# SCH_TRAILDEV.net
KiCad netlist of a schematic drawn in EasyEDA
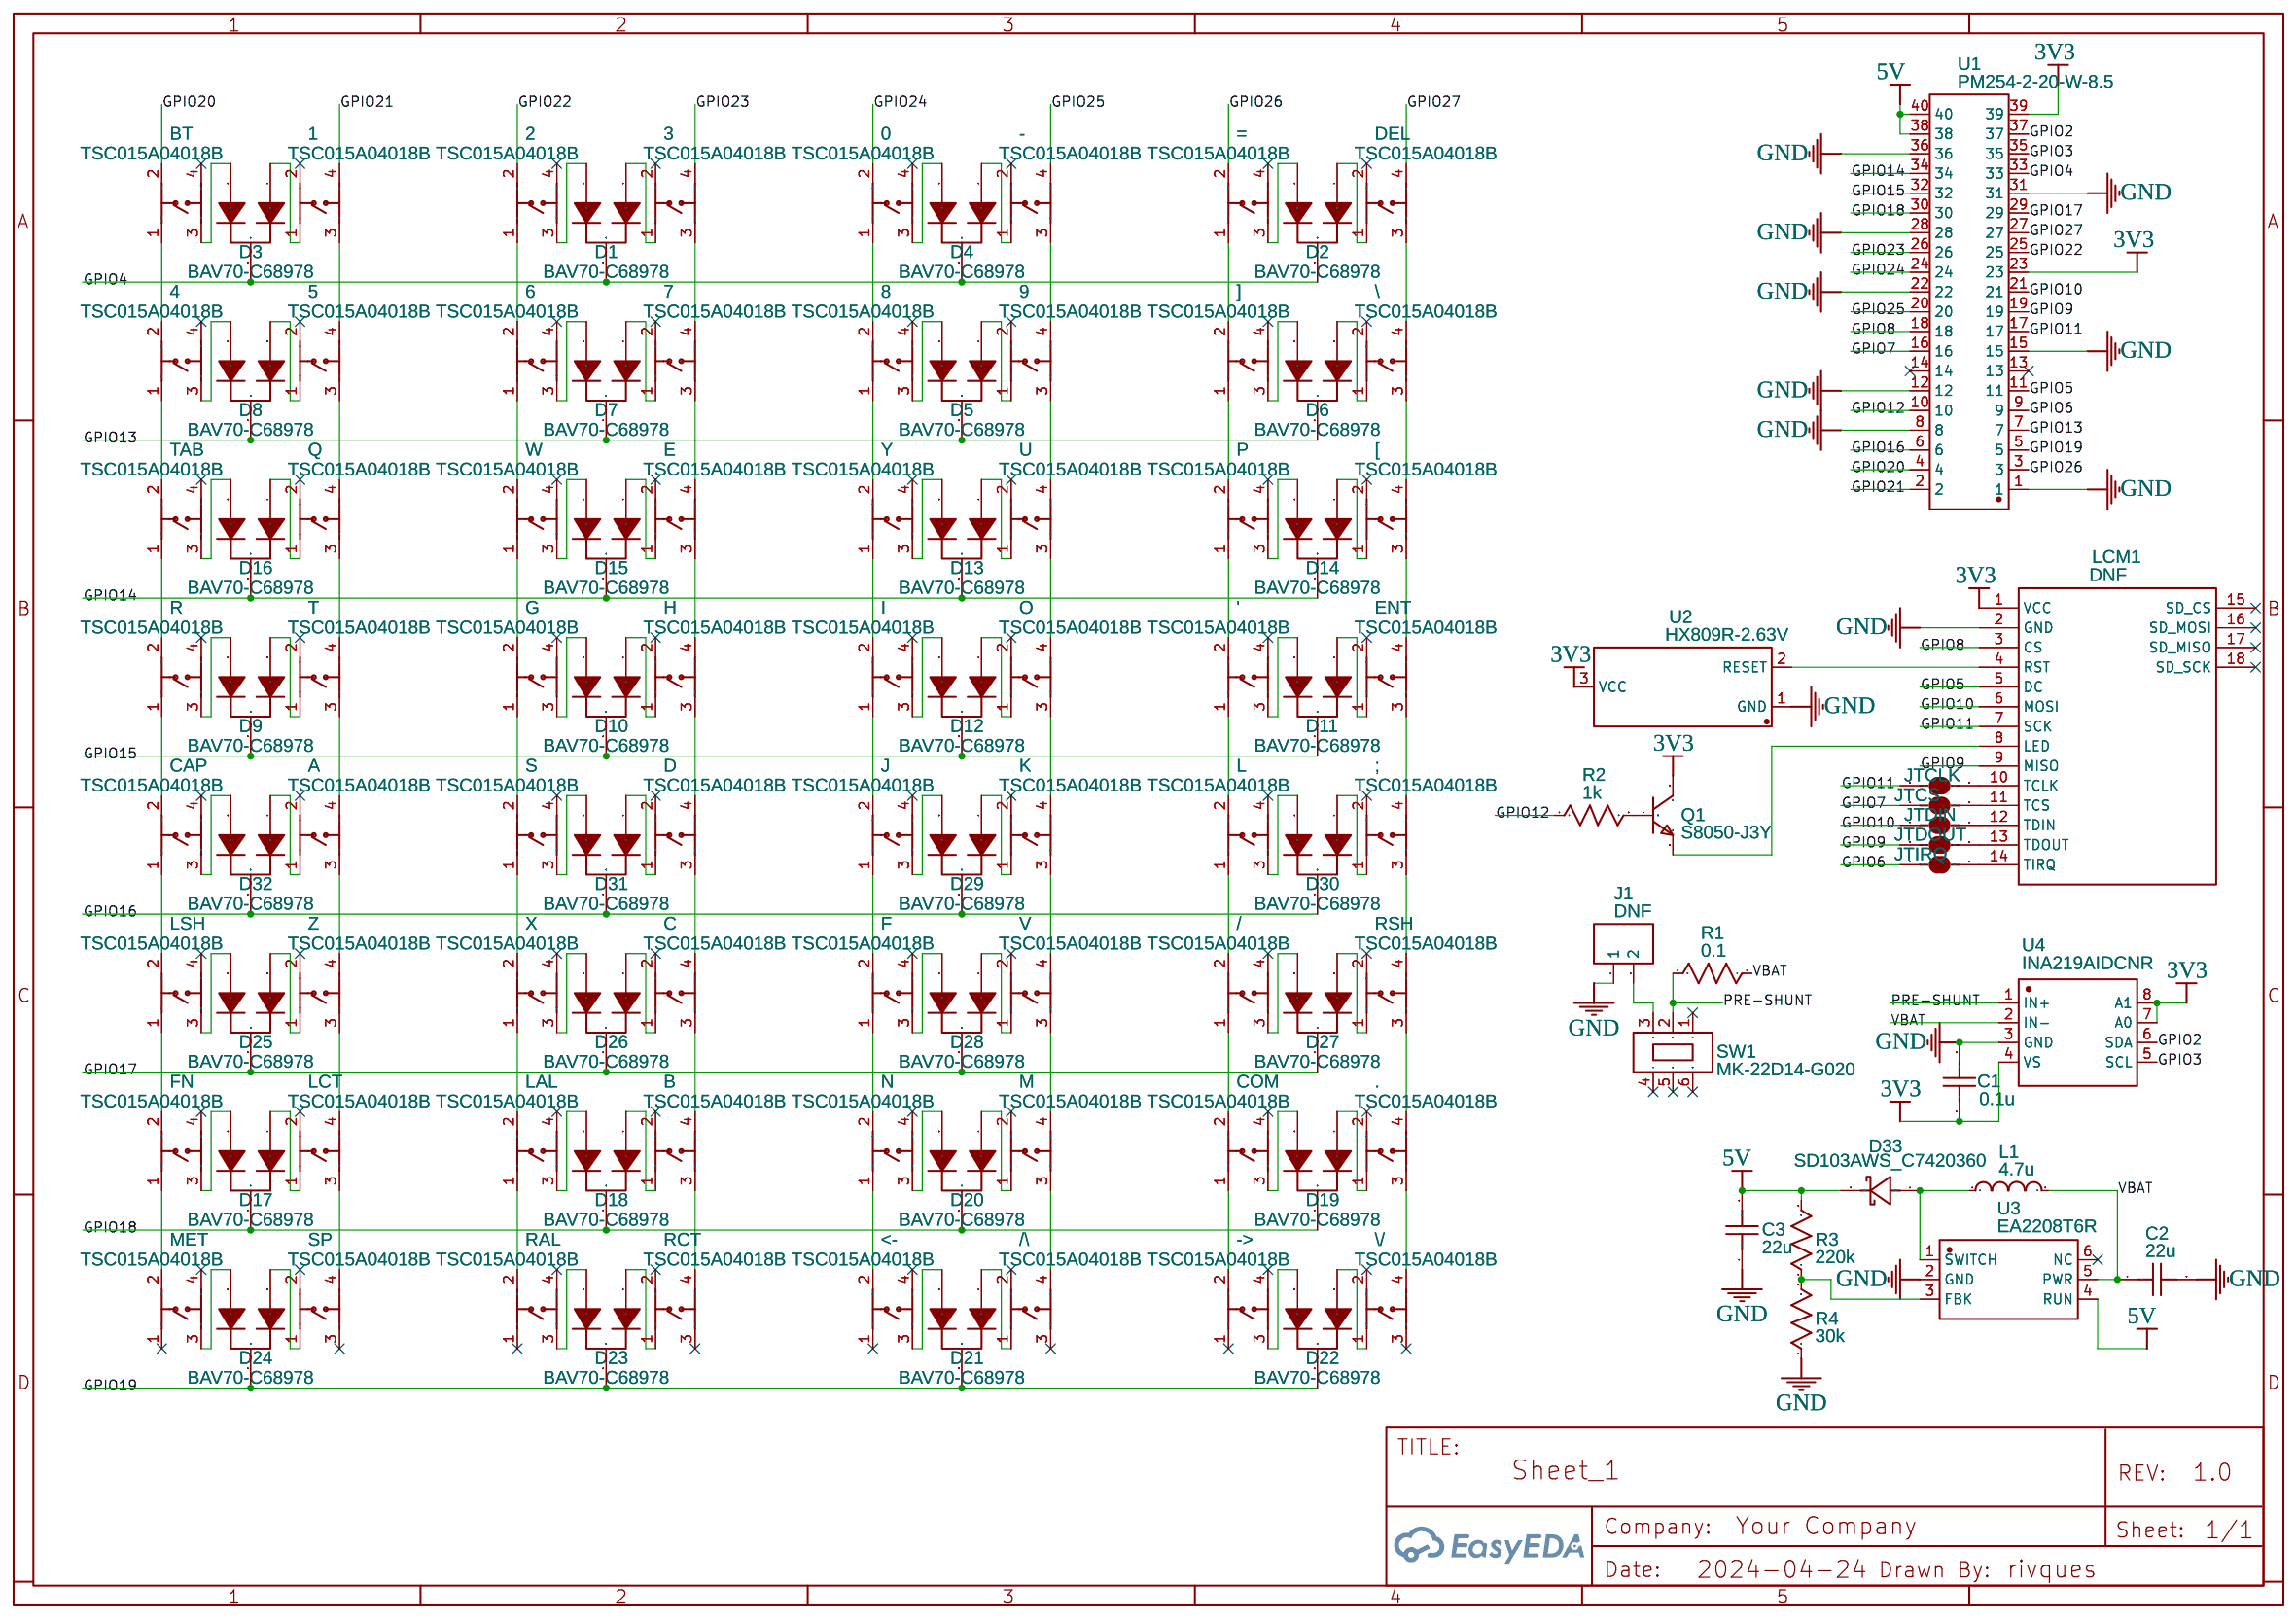
[diagram p0: schematic sheet]

(export (version "E")
  (design (tool "Eeschema 10.0.6"))
  (components
    (comp (ref "'")
      (value "TSC015A04018B")
      (fields (field (name "Manufacturer") "BZCN(博众电气)"))
      (libsource (lib "") (part "TSC015A04018B_53"))
    )
    (comp (ref "-")
      (value "TSC015A04018B")
      (fields (field (name "Manufacturer") "BZCN(博众电气)"))
      (libsource (lib "") (part "TSC015A04018B_41"))
    )
    (comp (ref "->")
      (value "TSC015A04018B")
      (fields (field (name "Manufacturer") "BZCN(博众电气)"))
      (libsource (lib "") (part "TSC015A04018B_29"))
    )
    (comp (ref ".")
      (value "TSC015A04018B")
      (fields (field (name "Manufacturer") "BZCN(博众电气)"))
      (libsource (lib "") (part "TSC015A04018B_6"))
    )
    (comp (ref "/")
      (value "TSC015A04018B")
      (fields (field (name "Manufacturer") "BZCN(博众电气)"))
      (libsource (lib "") (part "TSC015A04018B_22"))
    )
    (comp (ref "/\\")
      (value "TSC015A04018B")
      (fields (field (name "Manufacturer") "BZCN(博众电气)"))
      (libsource (lib "") (part "TSC015A04018B_28"))
    )
    (comp (ref "0")
      (value "TSC015A04018B")
      (fields (field (name "Manufacturer") "BZCN(博众电气)"))
      (libsource (lib "") (part "TSC015A04018B_3"))
    )
    (comp (ref "1")
      (value "TSC015A04018B")
      (fields (field (name "Manufacturer") "BZCN(博众电气)"))
      (libsource (lib "") (part "TSC015A04018B_3"))
    )
    (comp (ref "2")
      (value "TSC015A04018B")
      (fields (field (name "Manufacturer") "BZCN(博众电气)"))
      (libsource (lib "") (part "TSC015A04018B_3"))
    )
    (comp (ref "3")
      (value "TSC015A04018B")
      (fields (field (name "Manufacturer") "BZCN(博众电气)"))
      (libsource (lib "") (part "TSC015A04018B_3"))
    )
    (comp (ref "4")
      (value "TSC015A04018B")
      (fields (field (name "Manufacturer") "BZCN(博众电气)"))
      (libsource (lib "") (part "TSC015A04018B_3"))
    )
    (comp (ref "5")
      (value "TSC015A04018B")
      (fields (field (name "Manufacturer") "BZCN(博众电气)"))
      (libsource (lib "") (part "TSC015A04018B_3"))
    )
    (comp (ref "6")
      (value "TSC015A04018B")
      (fields (field (name "Manufacturer") "BZCN(博众电气)"))
      (libsource (lib "") (part "TSC015A04018B_3"))
    )
    (comp (ref "7")
      (value "TSC015A04018B")
      (fields (field (name "Manufacturer") "BZCN(博众电气)"))
      (libsource (lib "") (part "TSC015A04018B_3"))
    )
    (comp (ref "8")
      (value "TSC015A04018B")
      (fields (field (name "Manufacturer") "BZCN(博众电气)"))
      (libsource (lib "") (part "TSC015A04018B_3"))
    )
    (comp (ref "9")
      (value "TSC015A04018B")
      (fields (field (name "Manufacturer") "BZCN(博众电气)"))
      (libsource (lib "") (part "TSC015A04018B_3"))
    )
    (comp (ref ";")
      (value "TSC015A04018B")
      (fields (field (name "Manufacturer") "BZCN(博众电气)"))
      (libsource (lib "") (part "TSC015A04018B_48"))
    )
    (comp (ref "<-")
      (value "TSC015A04018B")
      (fields (field (name "Manufacturer") "BZCN(博众电气)"))
      (libsource (lib "") (part "TSC015A04018B_21"))
    )
    (comp (ref "=")
      (value "TSC015A04018B")
      (fields (field (name "Manufacturer") "BZCN(博众电气)"))
      (libsource (lib "") (part "TSC015A04018B_9"))
    )
    (comp (ref "A")
      (value "TSC015A04018B")
      (fields (field (name "Manufacturer Part") "?"))
      (libsource (lib "") (part "Unknown_0_-806"))
    )
    (comp (ref "B")
      (value "TSC015A04018B")
      (fields (field (name "Manufacturer") "BZCN(博众电气)"))
      (libsource (lib "") (part "TSC015A04018B_14"))
    )
    (comp (ref "BT")
      (value "TSC015A04018B")
      (fields (field (name "Manufacturer") "BZCN(博众电气)"))
      (libsource (lib "") (part "TSC015A04018B_38"))
    )
    (comp (ref "C")
      (value "TSC015A04018B")
      (fields (field (name "Manufacturer") "BZCN(博众电气)"))
      (libsource (lib "") (part "TSC015A04018B_39"))
    )
    (comp (ref "C1") (value "0.1u") (libsource (lib "") (part "C_0402_US")))
    (comp (ref "C2") (value "22u") (libsource (lib "") (part "C_0402_US_1")))
    (comp (ref "C3") (value "22u") (libsource (lib "") (part "C_0402_US")))
    (comp (ref "CAP")
      (value "TSC015A04018B")
      (fields (field (name "Manufacturer") "BZCN(博众电气)"))
      (libsource (lib "") (part "TSC015A04018B_5"))
    )
    (comp (ref "COM")
      (value "TSC015A04018B")
      (fields (field (name "Manufacturer") "BZCN(博众电气)"))
      (libsource (lib "") (part "TSC015A04018B_4"))
    )
    (comp (ref "D")
      (value "TSC015A04018B")
      (fields (field (name "Manufacturer") "BZCN(博众电气)"))
      (libsource (lib "") (part "TSC015A04018B_27"))
    )
    (comp (ref "D1")
      (value "BAV70-C68978")
      (fields (field (name "Manufacturer Part") "BAV70") (field (name "Manufacturer") "CJ(江苏长电/长晶)"))
      (libsource (lib "") (part "BAV70-C68978"))
    )
    (comp (ref "D2")
      (value "BAV70-C68978")
      (fields (field (name "Manufacturer Part") "BAV70") (field (name "Manufacturer") "CJ(江苏长电/长晶)"))
      (libsource (lib "") (part "BAV70-C68978"))
    )
    (comp (ref "D3")
      (value "BAV70-C68978")
      (fields (field (name "Manufacturer Part") "BAV70") (field (name "Manufacturer") "CJ(江苏长电/长晶)"))
      (libsource (lib "") (part "BAV70-C68978"))
    )
    (comp (ref "D4")
      (value "BAV70-C68978")
      (fields (field (name "Manufacturer Part") "BAV70") (field (name "Manufacturer") "CJ(江苏长电/长晶)"))
      (libsource (lib "") (part "BAV70-C68978"))
    )
    (comp (ref "D5")
      (value "BAV70-C68978")
      (fields (field (name "Manufacturer Part") "BAV70") (field (name "Manufacturer") "CJ(江苏长电/长晶)"))
      (libsource (lib "") (part "BAV70-C68978"))
    )
    (comp (ref "D6")
      (value "BAV70-C68978")
      (fields (field (name "Manufacturer Part") "BAV70") (field (name "Manufacturer") "CJ(江苏长电/长晶)"))
      (libsource (lib "") (part "BAV70-C68978"))
    )
    (comp (ref "D7")
      (value "BAV70-C68978")
      (fields (field (name "Manufacturer Part") "BAV70") (field (name "Manufacturer") "CJ(江苏长电/长晶)"))
      (libsource (lib "") (part "BAV70-C68978"))
    )
    (comp (ref "D8")
      (value "BAV70-C68978")
      (fields (field (name "Manufacturer Part") "BAV70") (field (name "Manufacturer") "CJ(江苏长电/长晶)"))
      (libsource (lib "") (part "BAV70-C68978"))
    )
    (comp (ref "D9")
      (value "BAV70-C68978")
      (fields (field (name "Manufacturer Part") "BAV70") (field (name "Manufacturer") "CJ(江苏长电/长晶)"))
      (libsource (lib "") (part "BAV70-C68978"))
    )
    (comp (ref "D10")
      (value "BAV70-C68978")
      (fields (field (name "Manufacturer Part") "BAV70") (field (name "Manufacturer") "CJ(江苏长电/长晶)"))
      (libsource (lib "") (part "BAV70-C68978"))
    )
    (comp (ref "D11")
      (value "BAV70-C68978")
      (fields (field (name "Manufacturer Part") "BAV70") (field (name "Manufacturer") "CJ(江苏长电/长晶)"))
      (libsource (lib "") (part "BAV70-C68978"))
    )
    (comp (ref "D12")
      (value "BAV70-C68978")
      (fields (field (name "Manufacturer Part") "BAV70") (field (name "Manufacturer") "CJ(江苏长电/长晶)"))
      (libsource (lib "") (part "BAV70-C68978"))
    )
    (comp (ref "D13")
      (value "BAV70-C68978")
      (fields (field (name "Manufacturer Part") "BAV70") (field (name "Manufacturer") "CJ(江苏长电/长晶)"))
      (libsource (lib "") (part "BAV70-C68978"))
    )
    (comp (ref "D14")
      (value "BAV70-C68978")
      (fields (field (name "Manufacturer Part") "BAV70") (field (name "Manufacturer") "CJ(江苏长电/长晶)"))
      (libsource (lib "") (part "BAV70-C68978"))
    )
    (comp (ref "D15")
      (value "BAV70-C68978")
      (fields (field (name "Manufacturer Part") "BAV70") (field (name "Manufacturer") "CJ(江苏长电/长晶)"))
      (libsource (lib "") (part "BAV70-C68978"))
    )
    (comp (ref "D16")
      (value "BAV70-C68978")
      (fields (field (name "Manufacturer Part") "BAV70") (field (name "Manufacturer") "CJ(江苏长电/长晶)"))
      (libsource (lib "") (part "BAV70-C68978"))
    )
    (comp (ref "D17")
      (value "BAV70-C68978")
      (fields (field (name "Manufacturer Part") "BAV70") (field (name "Manufacturer") "CJ(江苏长电/长晶)"))
      (libsource (lib "") (part "BAV70-C68978"))
    )
    (comp (ref "D18")
      (value "BAV70-C68978")
      (fields (field (name "Manufacturer Part") "BAV70") (field (name "Manufacturer") "CJ(江苏长电/长晶)"))
      (libsource (lib "") (part "BAV70-C68978"))
    )
    (comp (ref "D19")
      (value "BAV70-C68978")
      (fields (field (name "Manufacturer Part") "BAV70") (field (name "Manufacturer") "CJ(江苏长电/长晶)"))
      (libsource (lib "") (part "BAV70-C68978"))
    )
    (comp (ref "D20")
      (value "BAV70-C68978")
      (fields (field (name "Manufacturer Part") "BAV70") (field (name "Manufacturer") "CJ(江苏长电/长晶)"))
      (libsource (lib "") (part "BAV70-C68978"))
    )
    (comp (ref "D21")
      (value "BAV70-C68978")
      (fields (field (name "Manufacturer Part") "BAV70") (field (name "Manufacturer") "CJ(江苏长电/长晶)"))
      (libsource (lib "") (part "BAV70-C68978"))
    )
    (comp (ref "D22")
      (value "BAV70-C68978")
      (fields (field (name "Manufacturer Part") "BAV70") (field (name "Manufacturer") "CJ(江苏长电/长晶)"))
      (libsource (lib "") (part "BAV70-C68978"))
    )
    (comp (ref "D23")
      (value "BAV70-C68978")
      (fields (field (name "Manufacturer Part") "BAV70") (field (name "Manufacturer") "CJ(江苏长电/长晶)"))
      (libsource (lib "") (part "BAV70-C68978"))
    )
    (comp (ref "D24")
      (value "BAV70-C68978")
      (fields (field (name "Manufacturer Part") "BAV70") (field (name "Manufacturer") "CJ(江苏长电/长晶)"))
      (libsource (lib "") (part "BAV70-C68978"))
    )
    (comp (ref "D25")
      (value "BAV70-C68978")
      (fields (field (name "Manufacturer Part") "BAV70") (field (name "Manufacturer") "CJ(江苏长电/长晶)"))
      (libsource (lib "") (part "BAV70-C68978"))
    )
    (comp (ref "D26")
      (value "BAV70-C68978")
      (fields (field (name "Manufacturer Part") "BAV70") (field (name "Manufacturer") "CJ(江苏长电/长晶)"))
      (libsource (lib "") (part "BAV70-C68978"))
    )
    (comp (ref "D27")
      (value "BAV70-C68978")
      (fields (field (name "Manufacturer Part") "BAV70") (field (name "Manufacturer") "CJ(江苏长电/长晶)"))
      (libsource (lib "") (part "BAV70-C68978"))
    )
    (comp (ref "D28")
      (value "BAV70-C68978")
      (fields (field (name "Manufacturer Part") "BAV70") (field (name "Manufacturer") "CJ(江苏长电/长晶)"))
      (libsource (lib "") (part "BAV70-C68978"))
    )
    (comp (ref "D29")
      (value "BAV70-C68978")
      (fields (field (name "Manufacturer Part") "BAV70") (field (name "Manufacturer") "CJ(江苏长电/长晶)"))
      (libsource (lib "") (part "BAV70-C68978"))
    )
    (comp (ref "D30")
      (value "BAV70-C68978")
      (fields (field (name "Manufacturer Part") "BAV70") (field (name "Manufacturer") "CJ(江苏长电/长晶)"))
      (libsource (lib "") (part "BAV70-C68978"))
    )
    (comp (ref "D31")
      (value "BAV70-C68978")
      (fields (field (name "Manufacturer Part") "BAV70") (field (name "Manufacturer") "CJ(江苏长电/长晶)"))
      (libsource (lib "") (part "BAV70-C68978"))
    )
    (comp (ref "D32")
      (value "BAV70-C68978")
      (fields (field (name "Manufacturer Part") "BAV70") (field (name "Manufacturer") "CJ(江苏长电/长晶)"))
      (libsource (lib "") (part "BAV70-C68978"))
    )
    (comp (ref "D33")
      (value "SD103AWS_C7420360")
      (fields (field (name "Manufacturer Part") "SD103AWS") (field (name "Manufacturer") "宏迦橙"))
      (libsource (lib "") (part "SD103AWS_C7420360"))
    )
    (comp (ref "DEL")
      (value "TSC015A04018B")
      (fields (field (name "Manufacturer") "BZCN(博众电气)"))
      (libsource (lib "") (part "TSC015A04018B_40"))
    )
    (comp (ref "E")
      (value "TSC015A04018B")
      (fields (field (name "Manufacturer") "BZCN(博众电气)"))
      (libsource (lib "") (part "TSC015A04018B_7"))
    )
    (comp (ref "ENT")
      (value "TSC015A04018B")
      (fields (field (name "Manufacturer") "BZCN(博众电气)"))
      (libsource (lib "") (part "TSC015A04018B_24"))
    )
    (comp (ref "F")
      (value "TSC015A04018B")
      (fields (field (name "Manufacturer") "BZCN(博众电气)"))
      (libsource (lib "") (part "TSC015A04018B_36"))
    )
    (comp (ref "FN")
      (value "TSC015A04018B")
      (fields (field (name "Manufacturer") "BZCN(博众电气)"))
      (libsource (lib "") (part "TSC015A04018B_49"))
    )
    (comp (ref "G")
      (value "TSC015A04018B")
      (fields (field (name "Manufacturer") "BZCN(博众电气)"))
      (libsource (lib "") (part "TSC015A04018B_12"))
    )
    (comp (ref "H")
      (value "TSC015A04018B")
      (fields (field (name "Manufacturer") "BZCN(博众电气)"))
      (libsource (lib "") (part "TSC015A04018B_35"))
    )
    (comp (ref "I")
      (value "TSC015A04018B")
      (fields (field (name "Manufacturer") "BZCN(博众电气)"))
      (libsource (lib "") (part "TSC015A04018B_43"))
    )
    (comp (ref "J")
      (value "TSC015A04018B")
      (fields (field (name "Manufacturer") "BZCN(博众电气)"))
      (libsource (lib "") (part "TSC015A04018B_51"))
    )
    (comp (ref "J1") (value "DNF") (libsource (lib "") (part "HDR-M-2.54_1x2")))
    (comp (ref "JTCLK") (value "J-TCLK") (libsource (lib "") (part "SOLDERJUMPERTRACE_2")))
    (comp (ref "JTCS") (value "JUMPER") (libsource (lib "") (part "SOLDERJUMPERTRACE_3")))
    (comp (ref "JTDIN") (value "JUMPER") (libsource (lib "") (part "SOLDERJUMPERTRACE_1")))
    (comp (ref "JTDOUT") (value "JUMPER") (libsource (lib "") (part "SOLDERJUMPERTRACE_4")))
    (comp (ref "JTIRQ") (value "JUMPER") (libsource (lib "") (part "SOLDERJUMPERTRACE")))
    (comp (ref "K")
      (value "TSC015A04018B")
      (fields (field (name "Manufacturer") "BZCN(博众电气)"))
      (libsource (lib "") (part "TSC015A04018B_54"))
    )
    (comp (ref "L")
      (value "TSC015A04018B")
      (fields (field (name "Manufacturer") "BZCN(博众电气)"))
      (libsource (lib "") (part "TSC015A04018B_37"))
    )
    (comp (ref "L1") (value "4.7u") (libsource (lib "") (part "L0603_US")))
    (comp (ref "LAL")
      (value "TSC015A04018B")
      (fields (field (name "Manufacturer") "BZCN(博众电气)"))
      (libsource (lib "") (part "TSC015A04018B_31"))
    )
    (comp (ref "LCM1") (value "DNF") (libsource (lib "") (part "TFTSPI-2.8-240x320")))
    (comp (ref "LCT")
      (value "TSC015A04018B")
      (fields (field (name "Manufacturer") "BZCN(博众电气)"))
      (libsource (lib "") (part "TSC015A04018B_23"))
    )
    (comp (ref "LSH")
      (value "TSC015A04018B")
      (fields (field (name "Manufacturer") "BZCN(博众电气)"))
      (libsource (lib "") (part "TSC015A04018B_30"))
    )
    (comp (ref "M")
      (value "TSC015A04018B")
      (fields (field (name "Manufacturer") "BZCN(博众电气)"))
      (libsource (lib "") (part "TSC015A04018B_10"))
    )
    (comp (ref "MET")
      (value "TSC015A04018B")
      (fields (field (name "Manufacturer") "BZCN(博众电气)"))
      (libsource (lib "") (part "TSC015A04018B_47"))
    )
    (comp (ref "N")
      (value "TSC015A04018B")
      (fields (field (name "Manufacturer") "BZCN(博众电气)"))
      (libsource (lib "") (part "TSC015A04018B_46"))
    )
    (comp (ref "O")
      (value "TSC015A04018B")
      (fields (field (name "Manufacturer") "BZCN(博众电气)"))
      (libsource (lib "") (part "TSC015A04018B_34"))
    )
    (comp (ref "P")
      (value "TSC015A04018B")
      (fields (field (name "Manufacturer") "BZCN(博众电气)"))
      (libsource (lib "") (part "TSC015A04018B_13"))
    )
    (comp (ref "Q")
      (value "TSC015A04018B")
      (fields (field (name "Manufacturer") "BZCN(博众电气)"))
      (libsource (lib "") (part "TSC015A04018B_44"))
    )
    (comp (ref "Q1")
      (value "S8050-J3Y")
      (fields (field (name "Manufacturer") "MDD"))
      (libsource (lib "") (part "S8050-J3Y"))
    )
    (comp (ref "R")
      (value "TSC015A04018B")
      (fields (field (name "Manufacturer") "BZCN(博众电气)"))
      (libsource (lib "") (part "TSC015A04018B_52"))
    )
    (comp (ref "R1") (value "0.1") (libsource (lib "") (part "R_2512_US")))
    (comp (ref "R2") (value "1k") (libsource (lib "") (part "R_0402_US")))
    (comp (ref "R3") (value "220k") (libsource (lib "") (part "R_0603_US")))
    (comp (ref "R4") (value "30k") (libsource (lib "") (part "R_0603_US")))
    (comp (ref "RAL")
      (value "TSC015A04018B")
      (fields (field (name "Manufacturer") "BZCN(博众电气)"))
      (libsource (lib "") (part "TSC015A04018B"))
    )
    (comp (ref "RCT")
      (value "TSC015A04018B")
      (fields (field (name "Manufacturer") "BZCN(博众电气)"))
      (libsource (lib "") (part "TSC015A04018B_32"))
    )
    (comp (ref "RSH")
      (value "TSC015A04018B")
      (fields (field (name "Manufacturer") "BZCN(博众电气)"))
      (libsource (lib "") (part "TSC015A04018B_19"))
    )
    (comp (ref "S")
      (value "TSC015A04018B")
      (fields (field (name "Manufacturer") "BZCN(博众电气)"))
      (libsource (lib "") (part "TSC015A04018B_8"))
    )
    (comp (ref "SP")
      (value "TSC015A04018B")
      (fields (field (name "Manufacturer") "BZCN(博众电气)"))
      (libsource (lib "") (part "TSC015A04018B_25"))
    )
    (comp (ref "SW1")
      (value "MK-22D14-G020")
      (fields (field (name "Manufacturer") "G-Switch(品赞)"))
      (libsource (lib "") (part "MK-22D14-G020"))
    )
    (comp (ref "T")
      (value "TSC015A04018B")
      (fields (field (name "Manufacturer") "BZCN(博众电气)"))
      (libsource (lib "") (part "TSC015A04018B_26"))
    )
    (comp (ref "TAB")
      (value "TSC015A04018B")
      (fields (field (name "Manufacturer") "BZCN(博众电气)"))
      (libsource (lib "") (part "TSC015A04018B_18"))
    )
    (comp (ref "U")
      (value "TSC015A04018B")
      (fields (field (name "Manufacturer") "BZCN(博众电气)"))
      (libsource (lib "") (part "TSC015A04018B_1"))
    )
    (comp (ref "U1")
      (value "PM254-2-20-W-8.5")
      (fields (field (name "Manufacturer") "HCTL(华灿天禄)"))
      (libsource (lib "") (part "PM254-2-20-W-8.5"))
    )
    (comp (ref "U2")
      (value "HX809R-2.63V")
      (fields (field (name "Manufacturer") "HX(恒佳兴)"))
      (libsource (lib "") (part "HX809R-2.63V"))
    )
    (comp (ref "U3")
      (value "EA2208T6R")
      (fields (field (name "Manufacturer") "everanalog(申风)"))
      (libsource (lib "") (part "EA2208T6R"))
    )
    (comp (ref "U4")
      (value "INA219AIDCNR")
      (fields (field (name "Manufacturer") "TI(德州仪器)"))
      (libsource (lib "") (part "INA219AIDCNR"))
    )
    (comp (ref "V")
      (value "TSC015A04018B")
      (fields (field (name "Manufacturer") "BZCN(博众电气)"))
      (libsource (lib "") (part "TSC015A04018B_45"))
    )
    (comp (ref "W")
      (value "TSC015A04018B")
      (fields (field (name "Manufacturer") "BZCN(博众电气)"))
      (libsource (lib "") (part "TSC015A04018B_20"))
    )
    (comp (ref "X")
      (value "TSC015A04018B")
      (fields (field (name "Manufacturer") "BZCN(博众电气)"))
      (libsource (lib "") (part "TSC015A04018B_42"))
    )
    (comp (ref "Y")
      (value "TSC015A04018B")
      (fields (field (name "Manufacturer") "BZCN(博众电气)"))
      (libsource (lib "") (part "TSC015A04018B_15"))
    )
    (comp (ref "Z")
      (value "TSC015A04018B")
      (fields (field (name "Manufacturer") "BZCN(博众电气)"))
      (libsource (lib "") (part "TSC015A04018B_16"))
    )
    (comp (ref "[")
      (value "TSC015A04018B")
      (fields (field (name "Manufacturer") "BZCN(博众电气)"))
      (libsource (lib "") (part "TSC015A04018B_11"))
    )
    (comp (ref "\\")
      (value "TSC015A04018B")
      (fields (field (name "Manufacturer") "BZCN(博众电气)"))
      (libsource (lib "") (part "TSC015A04018B_50"))
    )
    (comp (ref "\\/")
      (value "TSC015A04018B")
      (fields (field (name "Manufacturer") "BZCN(博众电气)"))
      (libsource (lib "") (part "TSC015A04018B_17"))
    )
    (comp (ref "]")
      (value "TSC015A04018B")
      (fields (field (name "Manufacturer") "BZCN(博众电气)"))
      (libsource (lib "") (part "TSC015A04018B_2"))
    )
  )
  (nets
    (net (code "1") (name "/GPIO2") (class "Default")
      (node (ref "U1") (pin "37") (pinfunction "37_37") (pintype "unspecified"))
      (node (ref "U4") (pin "6") (pinfunction "SDA_6") (pintype "unspecified"))
    )
    (net (code "2") (name "/GPIO3") (class "Default")
      (node (ref "U1") (pin "35") (pinfunction "35_35") (pintype "unspecified"))
      (node (ref "U4") (pin "5") (pinfunction "SCL_5") (pintype "unspecified"))
    )
    (net (code "3") (name "/GPIO4") (class "Default")
      (node (ref "D1") (pin "3") (pinfunction "3_3") (pintype "unspecified"))
      (node (ref "D2") (pin "3") (pinfunction "3_3") (pintype "unspecified"))
      (node (ref "D3") (pin "3") (pinfunction "3_3") (pintype "unspecified"))
      (node (ref "D4") (pin "3") (pinfunction "3_3") (pintype "unspecified"))
      (node (ref "U1") (pin "33") (pinfunction "33_33") (pintype "unspecified"))
    )
    (net (code "4") (name "/GPIO5") (class "Default")
      (node (ref "LCM1") (pin "5") (pinfunction "DC_5") (pintype "unspecified"))
      (node (ref "U1") (pin "11") (pinfunction "11_11") (pintype "unspecified"))
    )
    (net (code "5") (name "/GPIO6") (class "Default")
      (node (ref "JTIRQ") (pin "1") (pinfunction "1_1") (pintype "unspecified"))
      (node (ref "U1") (pin "9") (pinfunction "9_9") (pintype "unspecified"))
    )
    (net (code "6") (name "/GPIO7") (class "Default")
      (node (ref "JTCS") (pin "1") (pinfunction "1_1") (pintype "unspecified"))
      (node (ref "U1") (pin "16") (pinfunction "16_16") (pintype "unspecified"))
    )
    (net (code "7") (name "/GPIO8") (class "Default")
      (node (ref "LCM1") (pin "3") (pinfunction "CS_3") (pintype "unspecified"))
      (node (ref "U1") (pin "18") (pinfunction "18_18") (pintype "unspecified"))
    )
    (net (code "8") (name "/GPIO9") (class "Default")
      (node (ref "JTDOUT") (pin "1") (pinfunction "1_1") (pintype "unspecified"))
      (node (ref "LCM1") (pin "9") (pinfunction "MISO_9") (pintype "unspecified"))
      (node (ref "U1") (pin "19") (pinfunction "19_19") (pintype "unspecified"))
    )
    (net (code "9") (name "/GPIO10") (class "Default")
      (node (ref "JTDIN") (pin "1") (pinfunction "1_1") (pintype "unspecified"))
      (node (ref "LCM1") (pin "6") (pinfunction "MOSI_6") (pintype "unspecified"))
      (node (ref "U1") (pin "21") (pinfunction "21_21") (pintype "unspecified"))
    )
    (net (code "10") (name "/GPIO11") (class "Default")
      (node (ref "JTCLK") (pin "1") (pinfunction "1_1") (pintype "unspecified"))
      (node (ref "LCM1") (pin "7") (pinfunction "SCK_7") (pintype "unspecified"))
      (node (ref "U1") (pin "17") (pinfunction "17_17") (pintype "unspecified"))
    )
    (net (code "11") (name "/GPIO12") (class "Default")
      (node (ref "R2") (pin "1") (pinfunction "1_1") (pintype "unspecified"))
      (node (ref "U1") (pin "10") (pinfunction "10_10") (pintype "unspecified"))
    )
    (net (code "12") (name "/GPIO13") (class "Default")
      (node (ref "D5") (pin "3") (pinfunction "3_3") (pintype "unspecified"))
      (node (ref "D6") (pin "3") (pinfunction "3_3") (pintype "unspecified"))
      (node (ref "D7") (pin "3") (pinfunction "3_3") (pintype "unspecified"))
      (node (ref "D8") (pin "3") (pinfunction "3_3") (pintype "unspecified"))
      (node (ref "U1") (pin "7") (pinfunction "7_7") (pintype "unspecified"))
    )
    (net (code "13") (name "/GPIO14") (class "Default")
      (node (ref "D13") (pin "3") (pinfunction "3_3") (pintype "unspecified"))
      (node (ref "D14") (pin "3") (pinfunction "3_3") (pintype "unspecified"))
      (node (ref "D15") (pin "3") (pinfunction "3_3") (pintype "unspecified"))
      (node (ref "D16") (pin "3") (pinfunction "3_3") (pintype "unspecified"))
      (node (ref "U1") (pin "34") (pinfunction "34_34") (pintype "unspecified"))
    )
    (net (code "14") (name "/GPIO15") (class "Default")
      (node (ref "D10") (pin "3") (pinfunction "3_3") (pintype "unspecified"))
      (node (ref "D11") (pin "3") (pinfunction "3_3") (pintype "unspecified"))
      (node (ref "D12") (pin "3") (pinfunction "3_3") (pintype "unspecified"))
      (node (ref "D9") (pin "3") (pinfunction "3_3") (pintype "unspecified"))
      (node (ref "U1") (pin "32") (pinfunction "32_32") (pintype "unspecified"))
    )
    (net (code "15") (name "/GPIO16") (class "Default")
      (node (ref "D29") (pin "3") (pinfunction "3_3") (pintype "unspecified"))
      (node (ref "D30") (pin "3") (pinfunction "3_3") (pintype "unspecified"))
      (node (ref "D31") (pin "3") (pinfunction "3_3") (pintype "unspecified"))
      (node (ref "D32") (pin "3") (pinfunction "3_3") (pintype "unspecified"))
      (node (ref "U1") (pin "6") (pinfunction "6_6") (pintype "unspecified"))
    )
    (net (code "16") (name "/GPIO17") (class "Default")
      (node (ref "D25") (pin "3") (pinfunction "3_3") (pintype "unspecified"))
      (node (ref "D26") (pin "3") (pinfunction "3_3") (pintype "unspecified"))
      (node (ref "D27") (pin "3") (pinfunction "3_3") (pintype "unspecified"))
      (node (ref "D28") (pin "3") (pinfunction "3_3") (pintype "unspecified"))
      (node (ref "U1") (pin "29") (pinfunction "29_29") (pintype "unspecified"))
    )
    (net (code "17") (name "/GPIO18") (class "Default")
      (node (ref "D17") (pin "3") (pinfunction "3_3") (pintype "unspecified"))
      (node (ref "D18") (pin "3") (pinfunction "3_3") (pintype "unspecified"))
      (node (ref "D19") (pin "3") (pinfunction "3_3") (pintype "unspecified"))
      (node (ref "D20") (pin "3") (pinfunction "3_3") (pintype "unspecified"))
      (node (ref "U1") (pin "30") (pinfunction "30_30") (pintype "unspecified"))
    )
    (net (code "18") (name "/GPIO19") (class "Default")
      (node (ref "D21") (pin "3") (pinfunction "3_3") (pintype "unspecified"))
      (node (ref "D22") (pin "3") (pinfunction "3_3") (pintype "unspecified"))
      (node (ref "D23") (pin "3") (pinfunction "3_3") (pintype "unspecified"))
      (node (ref "D24") (pin "3") (pinfunction "3_3") (pintype "unspecified"))
      (node (ref "U1") (pin "5") (pinfunction "5_5") (pintype "unspecified"))
    )
    (net (code "19") (name "/GPIO20") (class "Default")
      (node (ref "BT") (pin "2") (pinfunction "2_2") (pintype "unspecified"))
      (node (ref "U1") (pin "4") (pinfunction "4_4") (pintype "unspecified"))
    )
    (net (code "20") (name "/GPIO21") (class "Default")
      (node (ref "1") (pin "4") (pinfunction "4_4") (pintype "unspecified"))
      (node (ref "U1") (pin "2") (pinfunction "2_2") (pintype "unspecified"))
    )
    (net (code "21") (name "/GPIO22") (class "Default")
      (node (ref "2") (pin "2") (pinfunction "2_2") (pintype "unspecified"))
      (node (ref "U1") (pin "25") (pinfunction "25_25") (pintype "unspecified"))
    )
    (net (code "22") (name "/GPIO23") (class "Default")
      (node (ref "3") (pin "4") (pinfunction "4_4") (pintype "unspecified"))
      (node (ref "U1") (pin "26") (pinfunction "26_26") (pintype "unspecified"))
    )
    (net (code "23") (name "/GPIO24") (class "Default")
      (node (ref "0") (pin "2") (pinfunction "2_2") (pintype "unspecified"))
      (node (ref "U1") (pin "24") (pinfunction "24_24") (pintype "unspecified"))
    )
    (net (code "24") (name "/GPIO25") (class "Default")
      (node (ref "-") (pin "4") (pinfunction "4_4") (pintype "unspecified"))
      (node (ref "U1") (pin "20") (pinfunction "20_20") (pintype "unspecified"))
    )
    (net (code "25") (name "/GPIO26") (class "Default")
      (node (ref "=") (pin "2") (pinfunction "2_2") (pintype "unspecified"))
      (node (ref "U1") (pin "3") (pinfunction "3_3") (pintype "unspecified"))
    )
    (net (code "26") (name "/GPIO27") (class "Default")
      (node (ref "DEL") (pin "4") (pinfunction "4_4") (pintype "unspecified"))
      (node (ref "U1") (pin "27") (pinfunction "27_27") (pintype "unspecified"))
    )
    (net (code "27") (name "/PRE-SHUNT") (class "Default")
      (node (ref "R1") (pin "2") (pinfunction "2_2") (pintype "unspecified"))
      (node (ref "SW1") (pin "2") (pinfunction "2_2") (pintype "unspecified"))
      (node (ref "U4") (pin "1") (pinfunction "IN+_1") (pintype "unspecified"))
    )
    (net (code "28") (name "/VBAT") (class "Default")
      (node (ref "C2") (pin "1") (pinfunction "1_1") (pintype "unspecified"))
      (node (ref "L1") (pin "2") (pinfunction "2_2") (pintype "unspecified"))
      (node (ref "R1") (pin "1") (pinfunction "1_1") (pintype "unspecified"))
      (node (ref "U3") (pin "5") (pinfunction "PWR_5") (pintype "unspecified"))
      (node (ref "U4") (pin "2") (pinfunction "IN-_2") (pintype "unspecified"))
    )
    (net (code "29") (name "3V3") (class "Default")
      (node (ref "C1") (pin "1") (pinfunction "1_1") (pintype "unspecified"))
      (node (ref "LCM1") (pin "1") (pinfunction "VCC_1") (pintype "unspecified"))
      (node (ref "Q1") (pin "3") (pinfunction "C_3") (pintype "unspecified"))
      (node (ref "U1") (pin "23") (pinfunction "23_23") (pintype "unspecified"))
      (node (ref "U1") (pin "39") (pinfunction "39_39") (pintype "unspecified"))
      (node (ref "U2") (pin "3") (pinfunction "VCC_3") (pintype "unspecified"))
      (node (ref "U4") (pin "4") (pinfunction "VS_4") (pintype "unspecified"))
      (node (ref "U4") (pin "7") (pinfunction "A0_7") (pintype "unspecified"))
      (node (ref "U4") (pin "8") (pinfunction "A1_8") (pintype "unspecified"))
    )
    (net (code "30") (name "5V") (class "Default")
      (node (ref "C3") (pin "2") (pinfunction "2_2") (pintype "unspecified"))
      (node (ref "D33") (pin "2") (pinfunction "K_2") (pintype "unspecified"))
      (node (ref "R3") (pin "2") (pinfunction "2_2") (pintype "unspecified"))
      (node (ref "U1") (pin "38") (pinfunction "38_38") (pintype "unspecified"))
      (node (ref "U1") (pin "40") (pinfunction "40_40") (pintype "unspecified"))
      (node (ref "U3") (pin "4") (pinfunction "RUN_4") (pintype "unspecified"))
    )
    (net (code "31") (name "GND") (class "Default")
      (node (ref "C1") (pin "2") (pinfunction "2_2") (pintype "unspecified"))
      (node (ref "C2") (pin "2") (pinfunction "2_2") (pintype "unspecified"))
      (node (ref "C3") (pin "1") (pinfunction "1_1") (pintype "unspecified"))
      (node (ref "J1") (pin "1") (pinfunction "1_1") (pintype "unspecified"))
      (node (ref "LCM1") (pin "2") (pinfunction "GND_2") (pintype "unspecified"))
      (node (ref "R4") (pin "1") (pinfunction "1_1") (pintype "unspecified"))
      (node (ref "U1") (pin "1") (pinfunction "1_1") (pintype "unspecified"))
      (node (ref "U1") (pin "12") (pinfunction "12_12") (pintype "unspecified"))
      (node (ref "U1") (pin "15") (pinfunction "15_15") (pintype "unspecified"))
      (node (ref "U1") (pin "22") (pinfunction "22_22") (pintype "unspecified"))
      (node (ref "U1") (pin "28") (pinfunction "28_28") (pintype "unspecified"))
      (node (ref "U1") (pin "31") (pinfunction "31_31") (pintype "unspecified"))
      (node (ref "U1") (pin "36") (pinfunction "36_36") (pintype "unspecified"))
      (node (ref "U1") (pin "8") (pinfunction "8_8") (pintype "unspecified"))
      (node (ref "U2") (pin "1") (pinfunction "GND_1") (pintype "unspecified"))
      (node (ref "U3") (pin "2") (pinfunction "GND_2") (pintype "unspecified"))
      (node (ref "U4") (pin "3") (pinfunction "GND_3") (pintype "unspecified"))
    )
    (net (code "32") (name "Net-('-Pad1)") (class "Default")
      (node (ref "'") (pin "1") (pinfunction "1_1") (pintype "unspecified"))
      (node (ref "L") (pin "2") (pinfunction "2_2") (pintype "unspecified"))
    )
    (net (code "33") (name "Net-('-Pad2)") (class "Default")
      (node (ref "'") (pin "2") (pinfunction "2_2") (pintype "unspecified"))
      (node (ref "P") (pin "1") (pinfunction "1_1") (pintype "unspecified"))
    )
    (net (code "34") (name "Net-('-Pad3)") (class "Default")
      (node (ref "'") (pin "3") (pinfunction "3_3") (pintype "unspecified"))
      (node (ref "D11") (pin "2") (pinfunction "2_2") (pintype "unspecified"))
    )
    (net (code "35") (name "Net-(--Pad1)") (class "Default")
      (node (ref "-") (pin "1") (pinfunction "1_1") (pintype "unspecified"))
      (node (ref "D4") (pin "1") (pinfunction "1_1") (pintype "unspecified"))
    )
    (net (code "36") (name "Net-(--Pad3)") (class "Default")
      (node (ref "-") (pin "3") (pinfunction "3_3") (pintype "unspecified"))
      (node (ref "9") (pin "4") (pinfunction "4_4") (pintype "unspecified"))
    )
    (net (code "37") (name "Net-(->-Pad2)") (class "Default")
      (node (ref "->") (pin "2") (pinfunction "2_2") (pintype "unspecified"))
      (node (ref "COM") (pin "1") (pinfunction "1_1") (pintype "unspecified"))
    )
    (net (code "38") (name "Net-(->-Pad3)") (class "Default")
      (node (ref "->") (pin "3") (pinfunction "3_3") (pintype "unspecified"))
      (node (ref "D22") (pin "2") (pinfunction "2_2") (pintype "unspecified"))
    )
    (net (code "39") (name "Net-(.-Pad1)") (class "Default")
      (node (ref ".") (pin "1") (pinfunction "1_1") (pintype "unspecified"))
      (node (ref "D19") (pin "1") (pinfunction "1_1") (pintype "unspecified"))
    )
    (net (code "40") (name "Net-(.-Pad3)") (class "Default")
      (node (ref ".") (pin "3") (pinfunction "3_3") (pintype "unspecified"))
      (node (ref "\\/") (pin "4") (pinfunction "4_4") (pintype "unspecified"))
    )
    (net (code "41") (name "Net-(.-Pad4)") (class "Default")
      (node (ref ".") (pin "4") (pinfunction "4_4") (pintype "unspecified"))
      (node (ref "RSH") (pin "3") (pinfunction "3_3") (pintype "unspecified"))
    )
    (net (code "42") (name "Net-(/-Pad1)") (class "Default")
      (node (ref "/") (pin "1") (pinfunction "1_1") (pintype "unspecified"))
      (node (ref "COM") (pin "2") (pinfunction "2_2") (pintype "unspecified"))
    )
    (net (code "43") (name "Net-(/-Pad2)") (class "Default")
      (node (ref "/") (pin "2") (pinfunction "2_2") (pintype "unspecified"))
      (node (ref "L") (pin "1") (pinfunction "1_1") (pintype "unspecified"))
    )
    (net (code "44") (name "Net-(/-Pad3)") (class "Default")
      (node (ref "/") (pin "3") (pinfunction "3_3") (pintype "unspecified"))
      (node (ref "D27") (pin "2") (pinfunction "2_2") (pintype "unspecified"))
    )
    (net (code "45") (name "Net-(/\\-Pad1)") (class "Default")
      (node (ref "/\\") (pin "1") (pinfunction "1_1") (pintype "unspecified"))
      (node (ref "D21") (pin "1") (pinfunction "1_1") (pintype "unspecified"))
    )
    (net (code "46") (name "Net-(/\\-Pad4)") (class "Default")
      (node (ref "/\\") (pin "4") (pinfunction "4_4") (pintype "unspecified"))
      (node (ref "M") (pin "3") (pinfunction "3_3") (pintype "unspecified"))
    )
    (net (code "47") (name "Net-(0-Pad1)") (class "Default")
      (node (ref "0") (pin "1") (pinfunction "1_1") (pintype "unspecified"))
      (node (ref "8") (pin "2") (pinfunction "2_2") (pintype "unspecified"))
    )
    (net (code "48") (name "Net-(0-Pad3)") (class "Default")
      (node (ref "0") (pin "3") (pinfunction "3_3") (pintype "unspecified"))
      (node (ref "D4") (pin "2") (pinfunction "2_2") (pintype "unspecified"))
    )
    (net (code "49") (name "Net-(1-Pad1)") (class "Default")
      (node (ref "1") (pin "1") (pinfunction "1_1") (pintype "unspecified"))
      (node (ref "D3") (pin "1") (pinfunction "1_1") (pintype "unspecified"))
    )
    (net (code "50") (name "Net-(1-Pad3)") (class "Default")
      (node (ref "1") (pin "3") (pinfunction "3_3") (pintype "unspecified"))
      (node (ref "5") (pin "4") (pinfunction "4_4") (pintype "unspecified"))
    )
    (net (code "51") (name "Net-(2-Pad1)") (class "Default")
      (node (ref "2") (pin "1") (pinfunction "1_1") (pintype "unspecified"))
      (node (ref "6") (pin "2") (pinfunction "2_2") (pintype "unspecified"))
    )
    (net (code "52") (name "Net-(2-Pad3)") (class "Default")
      (node (ref "2") (pin "3") (pinfunction "3_3") (pintype "unspecified"))
      (node (ref "D1") (pin "2") (pinfunction "2_2") (pintype "unspecified"))
    )
    (net (code "53") (name "Net-(3-Pad1)") (class "Default")
      (node (ref "3") (pin "1") (pinfunction "1_1") (pintype "unspecified"))
      (node (ref "D1") (pin "1") (pinfunction "1_1") (pintype "unspecified"))
    )
    (net (code "54") (name "Net-(3-Pad3)") (class "Default")
      (node (ref "3") (pin "3") (pinfunction "3_3") (pintype "unspecified"))
      (node (ref "7") (pin "4") (pinfunction "4_4") (pintype "unspecified"))
    )
    (net (code "55") (name "Net-(4-Pad1)") (class "Default")
      (node (ref "4") (pin "1") (pinfunction "1_1") (pintype "unspecified"))
      (node (ref "TAB") (pin "2") (pinfunction "2_2") (pintype "unspecified"))
    )
    (net (code "56") (name "Net-(4-Pad2)") (class "Default")
      (node (ref "4") (pin "2") (pinfunction "2_2") (pintype "unspecified"))
      (node (ref "BT") (pin "1") (pinfunction "1_1") (pintype "unspecified"))
    )
    (net (code "57") (name "Net-(4-Pad3)") (class "Default")
      (node (ref "4") (pin "3") (pinfunction "3_3") (pintype "unspecified"))
      (node (ref "D8") (pin "2") (pinfunction "2_2") (pintype "unspecified"))
    )
    (net (code "58") (name "Net-(5-Pad1)") (class "Default")
      (node (ref "5") (pin "1") (pinfunction "1_1") (pintype "unspecified"))
      (node (ref "D8") (pin "1") (pinfunction "1_1") (pintype "unspecified"))
    )
    (net (code "59") (name "Net-(5-Pad3)") (class "Default")
      (node (ref "5") (pin "3") (pinfunction "3_3") (pintype "unspecified"))
      (node (ref "Q") (pin "4") (pinfunction "4_4") (pintype "unspecified"))
    )
    (net (code "60") (name "Net-(6-Pad1)") (class "Default")
      (node (ref "6") (pin "1") (pinfunction "1_1") (pintype "unspecified"))
      (node (ref "W") (pin "2") (pinfunction "2_2") (pintype "unspecified"))
    )
    (net (code "61") (name "Net-(6-Pad3)") (class "Default")
      (node (ref "6") (pin "3") (pinfunction "3_3") (pintype "unspecified"))
      (node (ref "D7") (pin "2") (pinfunction "2_2") (pintype "unspecified"))
    )
    (net (code "62") (name "Net-(7-Pad1)") (class "Default")
      (node (ref "7") (pin "1") (pinfunction "1_1") (pintype "unspecified"))
      (node (ref "D7") (pin "1") (pinfunction "1_1") (pintype "unspecified"))
    )
    (net (code "63") (name "Net-(7-Pad3)") (class "Default")
      (node (ref "7") (pin "3") (pinfunction "3_3") (pintype "unspecified"))
      (node (ref "E") (pin "4") (pinfunction "4_4") (pintype "unspecified"))
    )
    (net (code "64") (name "Net-(8-Pad1)") (class "Default")
      (node (ref "8") (pin "1") (pinfunction "1_1") (pintype "unspecified"))
      (node (ref "Y") (pin "2") (pinfunction "2_2") (pintype "unspecified"))
    )
    (net (code "65") (name "Net-(8-Pad3)") (class "Default")
      (node (ref "8") (pin "3") (pinfunction "3_3") (pintype "unspecified"))
      (node (ref "D5") (pin "2") (pinfunction "2_2") (pintype "unspecified"))
    )
    (net (code "66") (name "Net-(9-Pad1)") (class "Default")
      (node (ref "9") (pin "1") (pinfunction "1_1") (pintype "unspecified"))
      (node (ref "D5") (pin "1") (pinfunction "1_1") (pintype "unspecified"))
    )
    (net (code "67") (name "Net-(9-Pad3)") (class "Default")
      (node (ref "9") (pin "3") (pinfunction "3_3") (pintype "unspecified"))
      (node (ref "U") (pin "4") (pinfunction "4_4") (pintype "unspecified"))
    )
    (net (code "68") (name "Net-(;-Pad1)") (class "Default")
      (node (ref ";") (pin "1") (pinfunction "1_1") (pintype "unspecified"))
      (node (ref "D30") (pin "1") (pinfunction "1_1") (pintype "unspecified"))
    )
    (net (code "69") (name "Net-(;-Pad3)") (class "Default")
      (node (ref ";") (pin "3") (pinfunction "3_3") (pintype "unspecified"))
      (node (ref "RSH") (pin "4") (pinfunction "4_4") (pintype "unspecified"))
    )
    (net (code "70") (name "Net-(;-Pad4)") (class "Default")
      (node (ref ";") (pin "4") (pinfunction "4_4") (pintype "unspecified"))
      (node (ref "ENT") (pin "3") (pinfunction "3_3") (pintype "unspecified"))
    )
    (net (code "71") (name "Net-(<--Pad2)") (class "Default")
      (node (ref "<-") (pin "2") (pinfunction "2_2") (pintype "unspecified"))
      (node (ref "N") (pin "1") (pinfunction "1_1") (pintype "unspecified"))
    )
    (net (code "72") (name "Net-(<--Pad3)") (class "Default")
      (node (ref "<-") (pin "3") (pinfunction "3_3") (pintype "unspecified"))
      (node (ref "D21") (pin "2") (pinfunction "2_2") (pintype "unspecified"))
    )
    (net (code "73") (name "Net-(=-Pad1)") (class "Default")
      (node (ref "=") (pin "1") (pinfunction "1_1") (pintype "unspecified"))
      (node (ref "]") (pin "2") (pinfunction "2_2") (pintype "unspecified"))
    )
    (net (code "74") (name "Net-(=-Pad3)") (class "Default")
      (node (ref "=") (pin "3") (pinfunction "3_3") (pintype "unspecified"))
      (node (ref "D2") (pin "2") (pinfunction "2_2") (pintype "unspecified"))
    )
    (net (code "75") (name "Net-(A-Pad1)") (class "Default")
      (node (ref "A") (pin "1") (pinfunction "1_1") (pintype "unspecified"))
      (node (ref "D32") (pin "1") (pinfunction "1_1") (pintype "unspecified"))
    )
    (net (code "76") (name "Net-(A-Pad3)") (class "Default")
      (node (ref "A") (pin "3") (pinfunction "3_3") (pintype "unspecified"))
      (node (ref "Z") (pin "4") (pinfunction "4_4") (pintype "unspecified"))
    )
    (net (code "77") (name "Net-(A-Pad4)") (class "Default")
      (node (ref "A") (pin "4") (pinfunction "4_4") (pintype "unspecified"))
      (node (ref "T") (pin "3") (pinfunction "3_3") (pintype "unspecified"))
    )
    (net (code "78") (name "Net-(B-Pad1)") (class "Default")
      (node (ref "B") (pin "1") (pinfunction "1_1") (pintype "unspecified"))
      (node (ref "D18") (pin "1") (pinfunction "1_1") (pintype "unspecified"))
    )
    (net (code "79") (name "Net-(B-Pad3)") (class "Default")
      (node (ref "B") (pin "3") (pinfunction "3_3") (pintype "unspecified"))
      (node (ref "RCT") (pin "4") (pinfunction "4_4") (pintype "unspecified"))
    )
    (net (code "80") (name "Net-(B-Pad4)") (class "Default")
      (node (ref "B") (pin "4") (pinfunction "4_4") (pintype "unspecified"))
      (node (ref "C") (pin "3") (pinfunction "3_3") (pintype "unspecified"))
    )
    (net (code "81") (name "Net-(BT-Pad3)") (class "Default")
      (node (ref "BT") (pin "3") (pinfunction "3_3") (pintype "unspecified"))
      (node (ref "D3") (pin "2") (pinfunction "2_2") (pintype "unspecified"))
    )
    (net (code "82") (name "Net-(C-Pad1)") (class "Default")
      (node (ref "C") (pin "1") (pinfunction "1_1") (pintype "unspecified"))
      (node (ref "D26") (pin "1") (pinfunction "1_1") (pintype "unspecified"))
    )
    (net (code "83") (name "Net-(C-Pad4)") (class "Default")
      (node (ref "C") (pin "4") (pinfunction "4_4") (pintype "unspecified"))
      (node (ref "D") (pin "3") (pinfunction "3_3") (pintype "unspecified"))
    )
    (net (code "84") (name "Net-(CAP-Pad1)") (class "Default")
      (node (ref "CAP") (pin "1") (pinfunction "1_1") (pintype "unspecified"))
      (node (ref "LSH") (pin "2") (pinfunction "2_2") (pintype "unspecified"))
    )
    (net (code "85") (name "Net-(CAP-Pad2)") (class "Default")
      (node (ref "CAP") (pin "2") (pinfunction "2_2") (pintype "unspecified"))
      (node (ref "R") (pin "1") (pinfunction "1_1") (pintype "unspecified"))
    )
    (net (code "86") (name "Net-(CAP-Pad3)") (class "Default")
      (node (ref "CAP") (pin "3") (pinfunction "3_3") (pintype "unspecified"))
      (node (ref "D32") (pin "2") (pinfunction "2_2") (pintype "unspecified"))
    )
    (net (code "87") (name "Net-(COM-Pad3)") (class "Default")
      (node (ref "COM") (pin "3") (pinfunction "3_3") (pintype "unspecified"))
      (node (ref "D19") (pin "2") (pinfunction "2_2") (pintype "unspecified"))
    )
    (net (code "88") (name "Net-(D-Pad1)") (class "Default")
      (node (ref "D") (pin "1") (pinfunction "1_1") (pintype "unspecified"))
      (node (ref "D31") (pin "1") (pinfunction "1_1") (pintype "unspecified"))
    )
    (net (code "89") (name "Net-(D-Pad4)") (class "Default")
      (node (ref "D") (pin "4") (pinfunction "4_4") (pintype "unspecified"))
      (node (ref "H") (pin "3") (pinfunction "3_3") (pintype "unspecified"))
    )
    (net (code "90") (name "Net-(D2-Pad1)") (class "Default")
      (node (ref "D2") (pin "1") (pinfunction "1_1") (pintype "unspecified"))
      (node (ref "DEL") (pin "1") (pinfunction "1_1") (pintype "unspecified"))
    )
    (net (code "91") (name "Net-(D6-Pad1)") (class "Default")
      (node (ref "D6") (pin "1") (pinfunction "1_1") (pintype "unspecified"))
      (node (ref "\\") (pin "1") (pinfunction "1_1") (pintype "unspecified"))
    )
    (net (code "92") (name "Net-(D6-Pad2)") (class "Default")
      (node (ref "D6") (pin "2") (pinfunction "2_2") (pintype "unspecified"))
      (node (ref "]") (pin "3") (pinfunction "3_3") (pintype "unspecified"))
    )
    (net (code "93") (name "Net-(D9-Pad1)") (class "Default")
      (node (ref "D9") (pin "1") (pinfunction "1_1") (pintype "unspecified"))
      (node (ref "T") (pin "1") (pinfunction "1_1") (pintype "unspecified"))
    )
    (net (code "94") (name "Net-(D9-Pad2)") (class "Default")
      (node (ref "D9") (pin "2") (pinfunction "2_2") (pintype "unspecified"))
      (node (ref "R") (pin "3") (pinfunction "3_3") (pintype "unspecified"))
    )
    (net (code "95") (name "Net-(D10-Pad1)") (class "Default")
      (node (ref "D10") (pin "1") (pinfunction "1_1") (pintype "unspecified"))
      (node (ref "H") (pin "1") (pinfunction "1_1") (pintype "unspecified"))
    )
    (net (code "96") (name "Net-(D10-Pad2)") (class "Default")
      (node (ref "D10") (pin "2") (pinfunction "2_2") (pintype "unspecified"))
      (node (ref "G") (pin "3") (pinfunction "3_3") (pintype "unspecified"))
    )
    (net (code "97") (name "Net-(D11-Pad1)") (class "Default")
      (node (ref "D11") (pin "1") (pinfunction "1_1") (pintype "unspecified"))
      (node (ref "ENT") (pin "1") (pinfunction "1_1") (pintype "unspecified"))
    )
    (net (code "98") (name "Net-(D12-Pad1)") (class "Default")
      (node (ref "D12") (pin "1") (pinfunction "1_1") (pintype "unspecified"))
      (node (ref "O") (pin "1") (pinfunction "1_1") (pintype "unspecified"))
    )
    (net (code "99") (name "Net-(D12-Pad2)") (class "Default")
      (node (ref "D12") (pin "2") (pinfunction "2_2") (pintype "unspecified"))
      (node (ref "I") (pin "3") (pinfunction "3_3") (pintype "unspecified"))
    )
    (net (code "100") (name "Net-(D13-Pad1)") (class "Default")
      (node (ref "D13") (pin "1") (pinfunction "1_1") (pintype "unspecified"))
      (node (ref "U") (pin "1") (pinfunction "1_1") (pintype "unspecified"))
    )
    (net (code "101") (name "Net-(D13-Pad2)") (class "Default")
      (node (ref "D13") (pin "2") (pinfunction "2_2") (pintype "unspecified"))
      (node (ref "Y") (pin "3") (pinfunction "3_3") (pintype "unspecified"))
    )
    (net (code "102") (name "Net-(D14-Pad1)") (class "Default")
      (node (ref "D14") (pin "1") (pinfunction "1_1") (pintype "unspecified"))
      (node (ref "[") (pin "1") (pinfunction "1_1") (pintype "unspecified"))
    )
    (net (code "103") (name "Net-(D14-Pad2)") (class "Default")
      (node (ref "D14") (pin "2") (pinfunction "2_2") (pintype "unspecified"))
      (node (ref "P") (pin "3") (pinfunction "3_3") (pintype "unspecified"))
    )
    (net (code "104") (name "Net-(D15-Pad1)") (class "Default")
      (node (ref "D15") (pin "1") (pinfunction "1_1") (pintype "unspecified"))
      (node (ref "E") (pin "1") (pinfunction "1_1") (pintype "unspecified"))
    )
    (net (code "105") (name "Net-(D15-Pad2)") (class "Default")
      (node (ref "D15") (pin "2") (pinfunction "2_2") (pintype "unspecified"))
      (node (ref "W") (pin "3") (pinfunction "3_3") (pintype "unspecified"))
    )
    (net (code "106") (name "Net-(D16-Pad1)") (class "Default")
      (node (ref "D16") (pin "1") (pinfunction "1_1") (pintype "unspecified"))
      (node (ref "Q") (pin "1") (pinfunction "1_1") (pintype "unspecified"))
    )
    (net (code "107") (name "Net-(D16-Pad2)") (class "Default")
      (node (ref "D16") (pin "2") (pinfunction "2_2") (pintype "unspecified"))
      (node (ref "TAB") (pin "3") (pinfunction "3_3") (pintype "unspecified"))
    )
    (net (code "108") (name "Net-(D17-Pad1)") (class "Default")
      (node (ref "D17") (pin "1") (pinfunction "1_1") (pintype "unspecified"))
      (node (ref "LCT") (pin "1") (pinfunction "1_1") (pintype "unspecified"))
    )
    (net (code "109") (name "Net-(D17-Pad2)") (class "Default")
      (node (ref "D17") (pin "2") (pinfunction "2_2") (pintype "unspecified"))
      (node (ref "FN") (pin "3") (pinfunction "3_3") (pintype "unspecified"))
    )
    (net (code "110") (name "Net-(D18-Pad2)") (class "Default")
      (node (ref "D18") (pin "2") (pinfunction "2_2") (pintype "unspecified"))
      (node (ref "LAL") (pin "3") (pinfunction "3_3") (pintype "unspecified"))
    )
    (net (code "111") (name "Net-(D20-Pad1)") (class "Default")
      (node (ref "D20") (pin "1") (pinfunction "1_1") (pintype "unspecified"))
      (node (ref "M") (pin "1") (pinfunction "1_1") (pintype "unspecified"))
    )
    (net (code "112") (name "Net-(D20-Pad2)") (class "Default")
      (node (ref "D20") (pin "2") (pinfunction "2_2") (pintype "unspecified"))
      (node (ref "N") (pin "3") (pinfunction "3_3") (pintype "unspecified"))
    )
    (net (code "113") (name "Net-(D22-Pad1)") (class "Default")
      (node (ref "D22") (pin "1") (pinfunction "1_1") (pintype "unspecified"))
      (node (ref "\\/") (pin "1") (pinfunction "1_1") (pintype "unspecified"))
    )
    (net (code "114") (name "Net-(D23-Pad1)") (class "Default")
      (node (ref "D23") (pin "1") (pinfunction "1_1") (pintype "unspecified"))
      (node (ref "RCT") (pin "1") (pinfunction "1_1") (pintype "unspecified"))
    )
    (net (code "115") (name "Net-(D23-Pad2)") (class "Default")
      (node (ref "D23") (pin "2") (pinfunction "2_2") (pintype "unspecified"))
      (node (ref "RAL") (pin "3") (pinfunction "3_3") (pintype "unspecified"))
    )
    (net (code "116") (name "Net-(D24-Pad1)") (class "Default")
      (node (ref "D24") (pin "1") (pinfunction "1_1") (pintype "unspecified"))
      (node (ref "SP") (pin "1") (pinfunction "1_1") (pintype "unspecified"))
    )
    (net (code "117") (name "Net-(D24-Pad2)") (class "Default")
      (node (ref "D24") (pin "2") (pinfunction "2_2") (pintype "unspecified"))
      (node (ref "MET") (pin "3") (pinfunction "3_3") (pintype "unspecified"))
    )
    (net (code "118") (name "Net-(D25-Pad1)") (class "Default")
      (node (ref "D25") (pin "1") (pinfunction "1_1") (pintype "unspecified"))
      (node (ref "Z") (pin "1") (pinfunction "1_1") (pintype "unspecified"))
    )
    (net (code "119") (name "Net-(D25-Pad2)") (class "Default")
      (node (ref "D25") (pin "2") (pinfunction "2_2") (pintype "unspecified"))
      (node (ref "LSH") (pin "3") (pinfunction "3_3") (pintype "unspecified"))
    )
    (net (code "120") (name "Net-(D26-Pad2)") (class "Default")
      (node (ref "D26") (pin "2") (pinfunction "2_2") (pintype "unspecified"))
      (node (ref "X") (pin "3") (pinfunction "3_3") (pintype "unspecified"))
    )
    (net (code "121") (name "Net-(D27-Pad1)") (class "Default")
      (node (ref "D27") (pin "1") (pinfunction "1_1") (pintype "unspecified"))
      (node (ref "RSH") (pin "1") (pinfunction "1_1") (pintype "unspecified"))
    )
    (net (code "122") (name "Net-(D28-Pad1)") (class "Default")
      (node (ref "D28") (pin "1") (pinfunction "1_1") (pintype "unspecified"))
      (node (ref "V") (pin "1") (pinfunction "1_1") (pintype "unspecified"))
    )
    (net (code "123") (name "Net-(D28-Pad2)") (class "Default")
      (node (ref "D28") (pin "2") (pinfunction "2_2") (pintype "unspecified"))
      (node (ref "F") (pin "3") (pinfunction "3_3") (pintype "unspecified"))
    )
    (net (code "124") (name "Net-(D29-Pad1)") (class "Default")
      (node (ref "D29") (pin "1") (pinfunction "1_1") (pintype "unspecified"))
      (node (ref "K") (pin "1") (pinfunction "1_1") (pintype "unspecified"))
    )
    (net (code "125") (name "Net-(D29-Pad2)") (class "Default")
      (node (ref "D29") (pin "2") (pinfunction "2_2") (pintype "unspecified"))
      (node (ref "J") (pin "3") (pinfunction "3_3") (pintype "unspecified"))
    )
    (net (code "126") (name "Net-(D30-Pad2)") (class "Default")
      (node (ref "D30") (pin "2") (pinfunction "2_2") (pintype "unspecified"))
      (node (ref "L") (pin "3") (pinfunction "3_3") (pintype "unspecified"))
    )
    (net (code "127") (name "Net-(D31-Pad2)") (class "Default")
      (node (ref "D31") (pin "2") (pinfunction "2_2") (pintype "unspecified"))
      (node (ref "S") (pin "3") (pinfunction "3_3") (pintype "unspecified"))
    )
    (net (code "128") (name "Net-(D33-A)") (class "Default")
      (node (ref "D33") (pin "1") (pinfunction "A_1") (pintype "unspecified"))
      (node (ref "L1") (pin "1") (pinfunction "1_1") (pintype "unspecified"))
      (node (ref "U3") (pin "1") (pinfunction "SWITCH_1") (pintype "unspecified"))
    )
    (net (code "129") (name "Net-(DEL-Pad3)") (class "Default")
      (node (ref "DEL") (pin "3") (pinfunction "3_3") (pintype "unspecified"))
      (node (ref "\\") (pin "4") (pinfunction "4_4") (pintype "unspecified"))
    )
    (net (code "130") (name "Net-(E-Pad3)") (class "Default")
      (node (ref "E") (pin "3") (pinfunction "3_3") (pintype "unspecified"))
      (node (ref "H") (pin "4") (pinfunction "4_4") (pintype "unspecified"))
    )
    (net (code "131") (name "Net-(ENT-Pad4)") (class "Default")
      (node (ref "ENT") (pin "4") (pinfunction "4_4") (pintype "unspecified"))
      (node (ref "[") (pin "3") (pinfunction "3_3") (pintype "unspecified"))
    )
    (net (code "132") (name "Net-(F-Pad1)") (class "Default")
      (node (ref "F") (pin "1") (pinfunction "1_1") (pintype "unspecified"))
      (node (ref "N") (pin "2") (pinfunction "2_2") (pintype "unspecified"))
    )
    (net (code "133") (name "Net-(F-Pad2)") (class "Default")
      (node (ref "F") (pin "2") (pinfunction "2_2") (pintype "unspecified"))
      (node (ref "J") (pin "1") (pinfunction "1_1") (pintype "unspecified"))
    )
    (net (code "134") (name "Net-(FN-Pad1)") (class "Default")
      (node (ref "FN") (pin "1") (pinfunction "1_1") (pintype "unspecified"))
      (node (ref "MET") (pin "2") (pinfunction "2_2") (pintype "unspecified"))
    )
    (net (code "135") (name "Net-(FN-Pad2)") (class "Default")
      (node (ref "FN") (pin "2") (pinfunction "2_2") (pintype "unspecified"))
      (node (ref "LSH") (pin "1") (pinfunction "1_1") (pintype "unspecified"))
    )
    (net (code "136") (name "Net-(G-Pad1)") (class "Default")
      (node (ref "G") (pin "1") (pinfunction "1_1") (pintype "unspecified"))
      (node (ref "S") (pin "2") (pinfunction "2_2") (pintype "unspecified"))
    )
    (net (code "137") (name "Net-(G-Pad2)") (class "Default")
      (node (ref "G") (pin "2") (pinfunction "2_2") (pintype "unspecified"))
      (node (ref "W") (pin "1") (pinfunction "1_1") (pintype "unspecified"))
    )
    (net (code "138") (name "Net-(I-Pad1)") (class "Default")
      (node (ref "I") (pin "1") (pinfunction "1_1") (pintype "unspecified"))
      (node (ref "J") (pin "2") (pinfunction "2_2") (pintype "unspecified"))
    )
    (net (code "139") (name "Net-(I-Pad2)") (class "Default")
      (node (ref "I") (pin "2") (pinfunction "2_2") (pintype "unspecified"))
      (node (ref "Y") (pin "1") (pinfunction "1_1") (pintype "unspecified"))
    )
    (net (code "140") (name "Net-(J1-Pad2)") (class "Default")
      (node (ref "J1") (pin "2") (pinfunction "2_2") (pintype "unspecified"))
      (node (ref "SW1") (pin "3") (pinfunction "3_3") (pintype "unspecified"))
    )
    (net (code "141") (name "Net-(K-Pad3)") (class "Default")
      (node (ref "K") (pin "3") (pinfunction "3_3") (pintype "unspecified"))
      (node (ref "V") (pin "4") (pinfunction "4_4") (pintype "unspecified"))
    )
    (net (code "142") (name "Net-(K-Pad4)") (class "Default")
      (node (ref "K") (pin "4") (pinfunction "4_4") (pintype "unspecified"))
      (node (ref "O") (pin "3") (pinfunction "3_3") (pintype "unspecified"))
    )
    (net (code "143") (name "Net-(LAL-Pad1)") (class "Default")
      (node (ref "LAL") (pin "1") (pinfunction "1_1") (pintype "unspecified"))
      (node (ref "RAL") (pin "2") (pinfunction "2_2") (pintype "unspecified"))
    )
    (net (code "144") (name "Net-(LAL-Pad2)") (class "Default")
      (node (ref "LAL") (pin "2") (pinfunction "2_2") (pintype "unspecified"))
      (node (ref "X") (pin "1") (pinfunction "1_1") (pintype "unspecified"))
    )
    (net (code "145") (name "Net-(LCM1-LED)") (class "Default")
      (node (ref "LCM1") (pin "8") (pinfunction "LED_8") (pintype "unspecified"))
      (node (ref "Q1") (pin "2") (pinfunction "E_2") (pintype "unspecified"))
    )
    (net (code "146") (name "Net-(LCM1-RST)") (class "Default")
      (node (ref "LCM1") (pin "4") (pinfunction "RST_4") (pintype "unspecified"))
      (node (ref "U2") (pin "2") (pinfunction "RESET_2") (pintype "unspecified"))
    )
    (net (code "147") (name "Net-(LCM1-TCLK)") (class "Default")
      (node (ref "JTCLK") (pin "2") (pinfunction "2_2") (pintype "unspecified"))
      (node (ref "LCM1") (pin "10") (pinfunction "TCLK_10") (pintype "unspecified"))
    )
    (net (code "148") (name "Net-(LCM1-TCS)") (class "Default")
      (node (ref "JTCS") (pin "2") (pinfunction "2_2") (pintype "unspecified"))
      (node (ref "LCM1") (pin "11") (pinfunction "TCS_11") (pintype "unspecified"))
    )
    (net (code "149") (name "Net-(LCM1-TDIN)") (class "Default")
      (node (ref "JTDIN") (pin "2") (pinfunction "2_2") (pintype "unspecified"))
      (node (ref "LCM1") (pin "12") (pinfunction "TDIN_12") (pintype "unspecified"))
    )
    (net (code "150") (name "Net-(LCM1-TDOUT)") (class "Default")
      (node (ref "JTDOUT") (pin "2") (pinfunction "2_2") (pintype "unspecified"))
      (node (ref "LCM1") (pin "13") (pinfunction "TDOUT_13") (pintype "unspecified"))
    )
    (net (code "151") (name "Net-(LCM1-TIRQ)") (class "Default")
      (node (ref "JTIRQ") (pin "2") (pinfunction "2_2") (pintype "unspecified"))
      (node (ref "LCM1") (pin "14") (pinfunction "TIRQ_14") (pintype "unspecified"))
    )
    (net (code "152") (name "Net-(LCT-Pad3)") (class "Default")
      (node (ref "LCT") (pin "3") (pinfunction "3_3") (pintype "unspecified"))
      (node (ref "SP") (pin "4") (pinfunction "4_4") (pintype "unspecified"))
    )
    (net (code "153") (name "Net-(LCT-Pad4)") (class "Default")
      (node (ref "LCT") (pin "4") (pinfunction "4_4") (pintype "unspecified"))
      (node (ref "Z") (pin "3") (pinfunction "3_3") (pintype "unspecified"))
    )
    (net (code "154") (name "Net-(M-Pad4)") (class "Default")
      (node (ref "M") (pin "4") (pinfunction "4_4") (pintype "unspecified"))
      (node (ref "V") (pin "3") (pinfunction "3_3") (pintype "unspecified"))
    )
    (net (code "155") (name "Net-(O-Pad4)") (class "Default")
      (node (ref "O") (pin "4") (pinfunction "4_4") (pintype "unspecified"))
      (node (ref "U") (pin "3") (pinfunction "3_3") (pintype "unspecified"))
    )
    (net (code "156") (name "Net-(P-Pad2)") (class "Default")
      (node (ref "P") (pin "2") (pinfunction "2_2") (pintype "unspecified"))
      (node (ref "]") (pin "1") (pinfunction "1_1") (pintype "unspecified"))
    )
    (net (code "157") (name "Net-(Q-Pad3)") (class "Default")
      (node (ref "Q") (pin "3") (pinfunction "3_3") (pintype "unspecified"))
      (node (ref "T") (pin "4") (pinfunction "4_4") (pintype "unspecified"))
    )
    (net (code "158") (name "Net-(Q1-B)") (class "Default")
      (node (ref "Q1") (pin "1") (pinfunction "B_1") (pintype "unspecified"))
      (node (ref "R2") (pin "2") (pinfunction "2_2") (pintype "unspecified"))
    )
    (net (code "159") (name "Net-(R-Pad2)") (class "Default")
      (node (ref "R") (pin "2") (pinfunction "2_2") (pintype "unspecified"))
      (node (ref "TAB") (pin "1") (pinfunction "1_1") (pintype "unspecified"))
    )
    (net (code "160") (name "Net-(S-Pad1)") (class "Default")
      (node (ref "S") (pin "1") (pinfunction "1_1") (pintype "unspecified"))
      (node (ref "X") (pin "2") (pinfunction "2_2") (pintype "unspecified"))
    )
    (net (code "161") (name "Net-(U3-FBK)") (class "Default")
      (node (ref "R3") (pin "1") (pinfunction "1_1") (pintype "unspecified"))
      (node (ref "R4") (pin "2") (pinfunction "2_2") (pintype "unspecified"))
      (node (ref "U3") (pin "3") (pinfunction "FBK_3") (pintype "unspecified"))
    )
    (net (code "162") (name "Net-([-Pad4)") (class "Default")
      (node (ref "[") (pin "4") (pinfunction "4_4") (pintype "unspecified"))
      (node (ref "\\") (pin "3") (pinfunction "3_3") (pintype "unspecified"))
    )
    (net (code "163") (name "unconnected-('-Pad4)") (class "Default")
      (node (ref "'") (pin "4") (pinfunction "4_4") (pintype "unspecified+no_connect"))
    )
    (net (code "164") (name "unconnected-(--Pad2)") (class "Default")
      (node (ref "-") (pin "2") (pinfunction "2_2") (pintype "unspecified+no_connect"))
    )
    (net (code "165") (name "unconnected-(->-Pad1)") (class "Default")
      (node (ref "->") (pin "1") (pinfunction "1_1") (pintype "unspecified+no_connect"))
    )
    (net (code "166") (name "unconnected-(->-Pad4)") (class "Default")
      (node (ref "->") (pin "4") (pinfunction "4_4") (pintype "unspecified+no_connect"))
    )
    (net (code "167") (name "unconnected-(.-Pad2)") (class "Default")
      (node (ref ".") (pin "2") (pinfunction "2_2") (pintype "unspecified+no_connect"))
    )
    (net (code "168") (name "unconnected-(/-Pad4)") (class "Default")
      (node (ref "/") (pin "4") (pinfunction "4_4") (pintype "unspecified+no_connect"))
    )
    (net (code "169") (name "unconnected-(/\\-Pad2)") (class "Default")
      (node (ref "/\\") (pin "2") (pinfunction "2_2") (pintype "unspecified+no_connect"))
    )
    (net (code "170") (name "unconnected-(/\\-Pad3)") (class "Default")
      (node (ref "/\\") (pin "3") (pinfunction "3_3") (pintype "unspecified+no_connect"))
    )
    (net (code "171") (name "unconnected-(0-Pad4)") (class "Default")
      (node (ref "0") (pin "4") (pinfunction "4_4") (pintype "unspecified+no_connect"))
    )
    (net (code "172") (name "unconnected-(1-Pad2)") (class "Default")
      (node (ref "1") (pin "2") (pinfunction "2_2") (pintype "unspecified+no_connect"))
    )
    (net (code "173") (name "unconnected-(2-Pad4)") (class "Default")
      (node (ref "2") (pin "4") (pinfunction "4_4") (pintype "unspecified+no_connect"))
    )
    (net (code "174") (name "unconnected-(3-Pad2)") (class "Default")
      (node (ref "3") (pin "2") (pinfunction "2_2") (pintype "unspecified+no_connect"))
    )
    (net (code "175") (name "unconnected-(4-Pad4)") (class "Default")
      (node (ref "4") (pin "4") (pinfunction "4_4") (pintype "unspecified+no_connect"))
    )
    (net (code "176") (name "unconnected-(5-Pad2)") (class "Default")
      (node (ref "5") (pin "2") (pinfunction "2_2") (pintype "unspecified+no_connect"))
    )
    (net (code "177") (name "unconnected-(6-Pad4)") (class "Default")
      (node (ref "6") (pin "4") (pinfunction "4_4") (pintype "unspecified+no_connect"))
    )
    (net (code "178") (name "unconnected-(7-Pad2)") (class "Default")
      (node (ref "7") (pin "2") (pinfunction "2_2") (pintype "unspecified+no_connect"))
    )
    (net (code "179") (name "unconnected-(8-Pad4)") (class "Default")
      (node (ref "8") (pin "4") (pinfunction "4_4") (pintype "unspecified+no_connect"))
    )
    (net (code "180") (name "unconnected-(9-Pad2)") (class "Default")
      (node (ref "9") (pin "2") (pinfunction "2_2") (pintype "unspecified+no_connect"))
    )
    (net (code "181") (name "unconnected-(;-Pad2)") (class "Default")
      (node (ref ";") (pin "2") (pinfunction "2_2") (pintype "unspecified+no_connect"))
    )
    (net (code "182") (name "unconnected-(<--Pad1)") (class "Default")
      (node (ref "<-") (pin "1") (pinfunction "1_1") (pintype "unspecified+no_connect"))
    )
    (net (code "183") (name "unconnected-(<--Pad4)") (class "Default")
      (node (ref "<-") (pin "4") (pinfunction "4_4") (pintype "unspecified+no_connect"))
    )
    (net (code "184") (name "unconnected-(=-Pad4)") (class "Default")
      (node (ref "=") (pin "4") (pinfunction "4_4") (pintype "unspecified+no_connect"))
    )
    (net (code "185") (name "unconnected-(A-Pad2)") (class "Default")
      (node (ref "A") (pin "2") (pinfunction "2_2") (pintype "unspecified+no_connect"))
    )
    (net (code "186") (name "unconnected-(B-Pad2)") (class "Default")
      (node (ref "B") (pin "2") (pinfunction "2_2") (pintype "unspecified+no_connect"))
    )
    (net (code "187") (name "unconnected-(BT-Pad4)") (class "Default")
      (node (ref "BT") (pin "4") (pinfunction "4_4") (pintype "unspecified+no_connect"))
    )
    (net (code "188") (name "unconnected-(C-Pad2)") (class "Default")
      (node (ref "C") (pin "2") (pinfunction "2_2") (pintype "unspecified+no_connect"))
    )
    (net (code "189") (name "unconnected-(CAP-Pad4)") (class "Default")
      (node (ref "CAP") (pin "4") (pinfunction "4_4") (pintype "unspecified+no_connect"))
    )
    (net (code "190") (name "unconnected-(COM-Pad4)") (class "Default")
      (node (ref "COM") (pin "4") (pinfunction "4_4") (pintype "unspecified+no_connect"))
    )
    (net (code "191") (name "unconnected-(D-Pad2)") (class "Default")
      (node (ref "D") (pin "2") (pinfunction "2_2") (pintype "unspecified+no_connect"))
    )
    (net (code "192") (name "unconnected-(DEL-Pad2)") (class "Default")
      (node (ref "DEL") (pin "2") (pinfunction "2_2") (pintype "unspecified+no_connect"))
    )
    (net (code "193") (name "unconnected-(E-Pad2)") (class "Default")
      (node (ref "E") (pin "2") (pinfunction "2_2") (pintype "unspecified+no_connect"))
    )
    (net (code "194") (name "unconnected-(ENT-Pad2)") (class "Default")
      (node (ref "ENT") (pin "2") (pinfunction "2_2") (pintype "unspecified+no_connect"))
    )
    (net (code "195") (name "unconnected-(F-Pad4)") (class "Default")
      (node (ref "F") (pin "4") (pinfunction "4_4") (pintype "unspecified+no_connect"))
    )
    (net (code "196") (name "unconnected-(FN-Pad4)") (class "Default")
      (node (ref "FN") (pin "4") (pinfunction "4_4") (pintype "unspecified+no_connect"))
    )
    (net (code "197") (name "unconnected-(G-Pad4)") (class "Default")
      (node (ref "G") (pin "4") (pinfunction "4_4") (pintype "unspecified+no_connect"))
    )
    (net (code "198") (name "unconnected-(H-Pad2)") (class "Default")
      (node (ref "H") (pin "2") (pinfunction "2_2") (pintype "unspecified+no_connect"))
    )
    (net (code "199") (name "unconnected-(I-Pad4)") (class "Default")
      (node (ref "I") (pin "4") (pinfunction "4_4") (pintype "unspecified+no_connect"))
    )
    (net (code "200") (name "unconnected-(J-Pad4)") (class "Default")
      (node (ref "J") (pin "4") (pinfunction "4_4") (pintype "unspecified+no_connect"))
    )
    (net (code "201") (name "unconnected-(K-Pad2)") (class "Default")
      (node (ref "K") (pin "2") (pinfunction "2_2") (pintype "unspecified+no_connect"))
    )
    (net (code "202") (name "unconnected-(L-Pad4)") (class "Default")
      (node (ref "L") (pin "4") (pinfunction "4_4") (pintype "unspecified+no_connect"))
    )
    (net (code "203") (name "unconnected-(LAL-Pad4)") (class "Default")
      (node (ref "LAL") (pin "4") (pinfunction "4_4") (pintype "unspecified+no_connect"))
    )
    (net (code "204") (name "unconnected-(LCM1-SD_CS-Pad15)") (class "Default")
      (node (ref "LCM1") (pin "15") (pinfunction "SD_CS_15") (pintype "unspecified+no_connect"))
    )
    (net (code "205") (name "unconnected-(LCM1-SD_MISO-Pad17)") (class "Default")
      (node (ref "LCM1") (pin "17") (pinfunction "SD_MISO_17") (pintype "unspecified+no_connect"))
    )
    (net (code "206") (name "unconnected-(LCM1-SD_MOSI-Pad16)") (class "Default")
      (node (ref "LCM1") (pin "16") (pinfunction "SD_MOSI_16") (pintype "unspecified+no_connect"))
    )
    (net (code "207") (name "unconnected-(LCM1-SD_SCK-Pad18)") (class "Default")
      (node (ref "LCM1") (pin "18") (pinfunction "SD_SCK_18") (pintype "unspecified+no_connect"))
    )
    (net (code "208") (name "unconnected-(LCT-Pad2)") (class "Default")
      (node (ref "LCT") (pin "2") (pinfunction "2_2") (pintype "unspecified+no_connect"))
    )
    (net (code "209") (name "unconnected-(LSH-Pad4)") (class "Default")
      (node (ref "LSH") (pin "4") (pinfunction "4_4") (pintype "unspecified+no_connect"))
    )
    (net (code "210") (name "unconnected-(M-Pad2)") (class "Default")
      (node (ref "M") (pin "2") (pinfunction "2_2") (pintype "unspecified+no_connect"))
    )
    (net (code "211") (name "unconnected-(MET-Pad1)") (class "Default")
      (node (ref "MET") (pin "1") (pinfunction "1_1") (pintype "unspecified+no_connect"))
    )
    (net (code "212") (name "unconnected-(MET-Pad4)") (class "Default")
      (node (ref "MET") (pin "4") (pinfunction "4_4") (pintype "unspecified+no_connect"))
    )
    (net (code "213") (name "unconnected-(N-Pad4)") (class "Default")
      (node (ref "N") (pin "4") (pinfunction "4_4") (pintype "unspecified+no_connect"))
    )
    (net (code "214") (name "unconnected-(O-Pad2)") (class "Default")
      (node (ref "O") (pin "2") (pinfunction "2_2") (pintype "unspecified+no_connect"))
    )
    (net (code "215") (name "unconnected-(P-Pad4)") (class "Default")
      (node (ref "P") (pin "4") (pinfunction "4_4") (pintype "unspecified+no_connect"))
    )
    (net (code "216") (name "unconnected-(Q-Pad2)") (class "Default")
      (node (ref "Q") (pin "2") (pinfunction "2_2") (pintype "unspecified+no_connect"))
    )
    (net (code "217") (name "unconnected-(R-Pad4)") (class "Default")
      (node (ref "R") (pin "4") (pinfunction "4_4") (pintype "unspecified+no_connect"))
    )
    (net (code "218") (name "unconnected-(RAL-Pad1)") (class "Default")
      (node (ref "RAL") (pin "1") (pinfunction "1_1") (pintype "unspecified+no_connect"))
    )
    (net (code "219") (name "unconnected-(RAL-Pad4)") (class "Default")
      (node (ref "RAL") (pin "4") (pinfunction "4_4") (pintype "unspecified+no_connect"))
    )
    (net (code "220") (name "unconnected-(RCT-Pad2)") (class "Default")
      (node (ref "RCT") (pin "2") (pinfunction "2_2") (pintype "unspecified+no_connect"))
    )
    (net (code "221") (name "unconnected-(RCT-Pad3)") (class "Default")
      (node (ref "RCT") (pin "3") (pinfunction "3_3") (pintype "unspecified+no_connect"))
    )
    (net (code "222") (name "unconnected-(RSH-Pad2)") (class "Default")
      (node (ref "RSH") (pin "2") (pinfunction "2_2") (pintype "unspecified+no_connect"))
    )
    (net (code "223") (name "unconnected-(S-Pad4)") (class "Default")
      (node (ref "S") (pin "4") (pinfunction "4_4") (pintype "unspecified+no_connect"))
    )
    (net (code "224") (name "unconnected-(SP-Pad2)") (class "Default")
      (node (ref "SP") (pin "2") (pinfunction "2_2") (pintype "unspecified+no_connect"))
    )
    (net (code "225") (name "unconnected-(SP-Pad3)") (class "Default")
      (node (ref "SP") (pin "3") (pinfunction "3_3") (pintype "unspecified+no_connect"))
    )
    (net (code "226") (name "unconnected-(SW1-Pad1)") (class "Default")
      (node (ref "SW1") (pin "1") (pinfunction "1_1") (pintype "unspecified+no_connect"))
    )
    (net (code "227") (name "unconnected-(SW1-Pad4)") (class "Default")
      (node (ref "SW1") (pin "4") (pinfunction "4_4") (pintype "unspecified+no_connect"))
    )
    (net (code "228") (name "unconnected-(SW1-Pad5)") (class "Default")
      (node (ref "SW1") (pin "5") (pinfunction "5_5") (pintype "unspecified+no_connect"))
    )
    (net (code "229") (name "unconnected-(SW1-Pad6)") (class "Default")
      (node (ref "SW1") (pin "6") (pinfunction "6_6") (pintype "unspecified+no_connect"))
    )
    (net (code "230") (name "unconnected-(T-Pad2)") (class "Default")
      (node (ref "T") (pin "2") (pinfunction "2_2") (pintype "unspecified+no_connect"))
    )
    (net (code "231") (name "unconnected-(TAB-Pad4)") (class "Default")
      (node (ref "TAB") (pin "4") (pinfunction "4_4") (pintype "unspecified+no_connect"))
    )
    (net (code "232") (name "unconnected-(U-Pad2)") (class "Default")
      (node (ref "U") (pin "2") (pinfunction "2_2") (pintype "unspecified+no_connect"))
    )
    (net (code "233") (name "unconnected-(U1-Pad13)") (class "Default")
      (node (ref "U1") (pin "13") (pinfunction "13_13") (pintype "unspecified+no_connect"))
    )
    (net (code "234") (name "unconnected-(U1-Pad14)") (class "Default")
      (node (ref "U1") (pin "14") (pinfunction "14_14") (pintype "unspecified+no_connect"))
    )
    (net (code "235") (name "unconnected-(U3-NC-Pad6)") (class "Default")
      (node (ref "U3") (pin "6") (pinfunction "NC_6") (pintype "unspecified+no_connect"))
    )
    (net (code "236") (name "unconnected-(V-Pad2)") (class "Default")
      (node (ref "V") (pin "2") (pinfunction "2_2") (pintype "unspecified+no_connect"))
    )
    (net (code "237") (name "unconnected-(W-Pad4)") (class "Default")
      (node (ref "W") (pin "4") (pinfunction "4_4") (pintype "unspecified+no_connect"))
    )
    (net (code "238") (name "unconnected-(X-Pad4)") (class "Default")
      (node (ref "X") (pin "4") (pinfunction "4_4") (pintype "unspecified+no_connect"))
    )
    (net (code "239") (name "unconnected-(Y-Pad4)") (class "Default")
      (node (ref "Y") (pin "4") (pinfunction "4_4") (pintype "unspecified+no_connect"))
    )
    (net (code "240") (name "unconnected-(Z-Pad2)") (class "Default")
      (node (ref "Z") (pin "2") (pinfunction "2_2") (pintype "unspecified+no_connect"))
    )
    (net (code "241") (name "unconnected-([-Pad2)") (class "Default")
      (node (ref "[") (pin "2") (pinfunction "2_2") (pintype "unspecified+no_connect"))
    )
    (net (code "242") (name "unconnected-(\\-Pad2)") (class "Default")
      (node (ref "\\") (pin "2") (pinfunction "2_2") (pintype "unspecified+no_connect"))
    )
    (net (code "243") (name "unconnected-(\\/-Pad2)") (class "Default")
      (node (ref "\\/") (pin "2") (pinfunction "2_2") (pintype "unspecified+no_connect"))
    )
    (net (code "244") (name "unconnected-(\\/-Pad3)") (class "Default")
      (node (ref "\\/") (pin "3") (pinfunction "3_3") (pintype "unspecified+no_connect"))
    )
    (net (code "245") (name "unconnected-(]-Pad4)") (class "Default")
      (node (ref "]") (pin "4") (pinfunction "4_4") (pintype "unspecified+no_connect"))
    )
  )
)
